# Comm.net
KiCad netlist of a schematic drawn in EAGLE
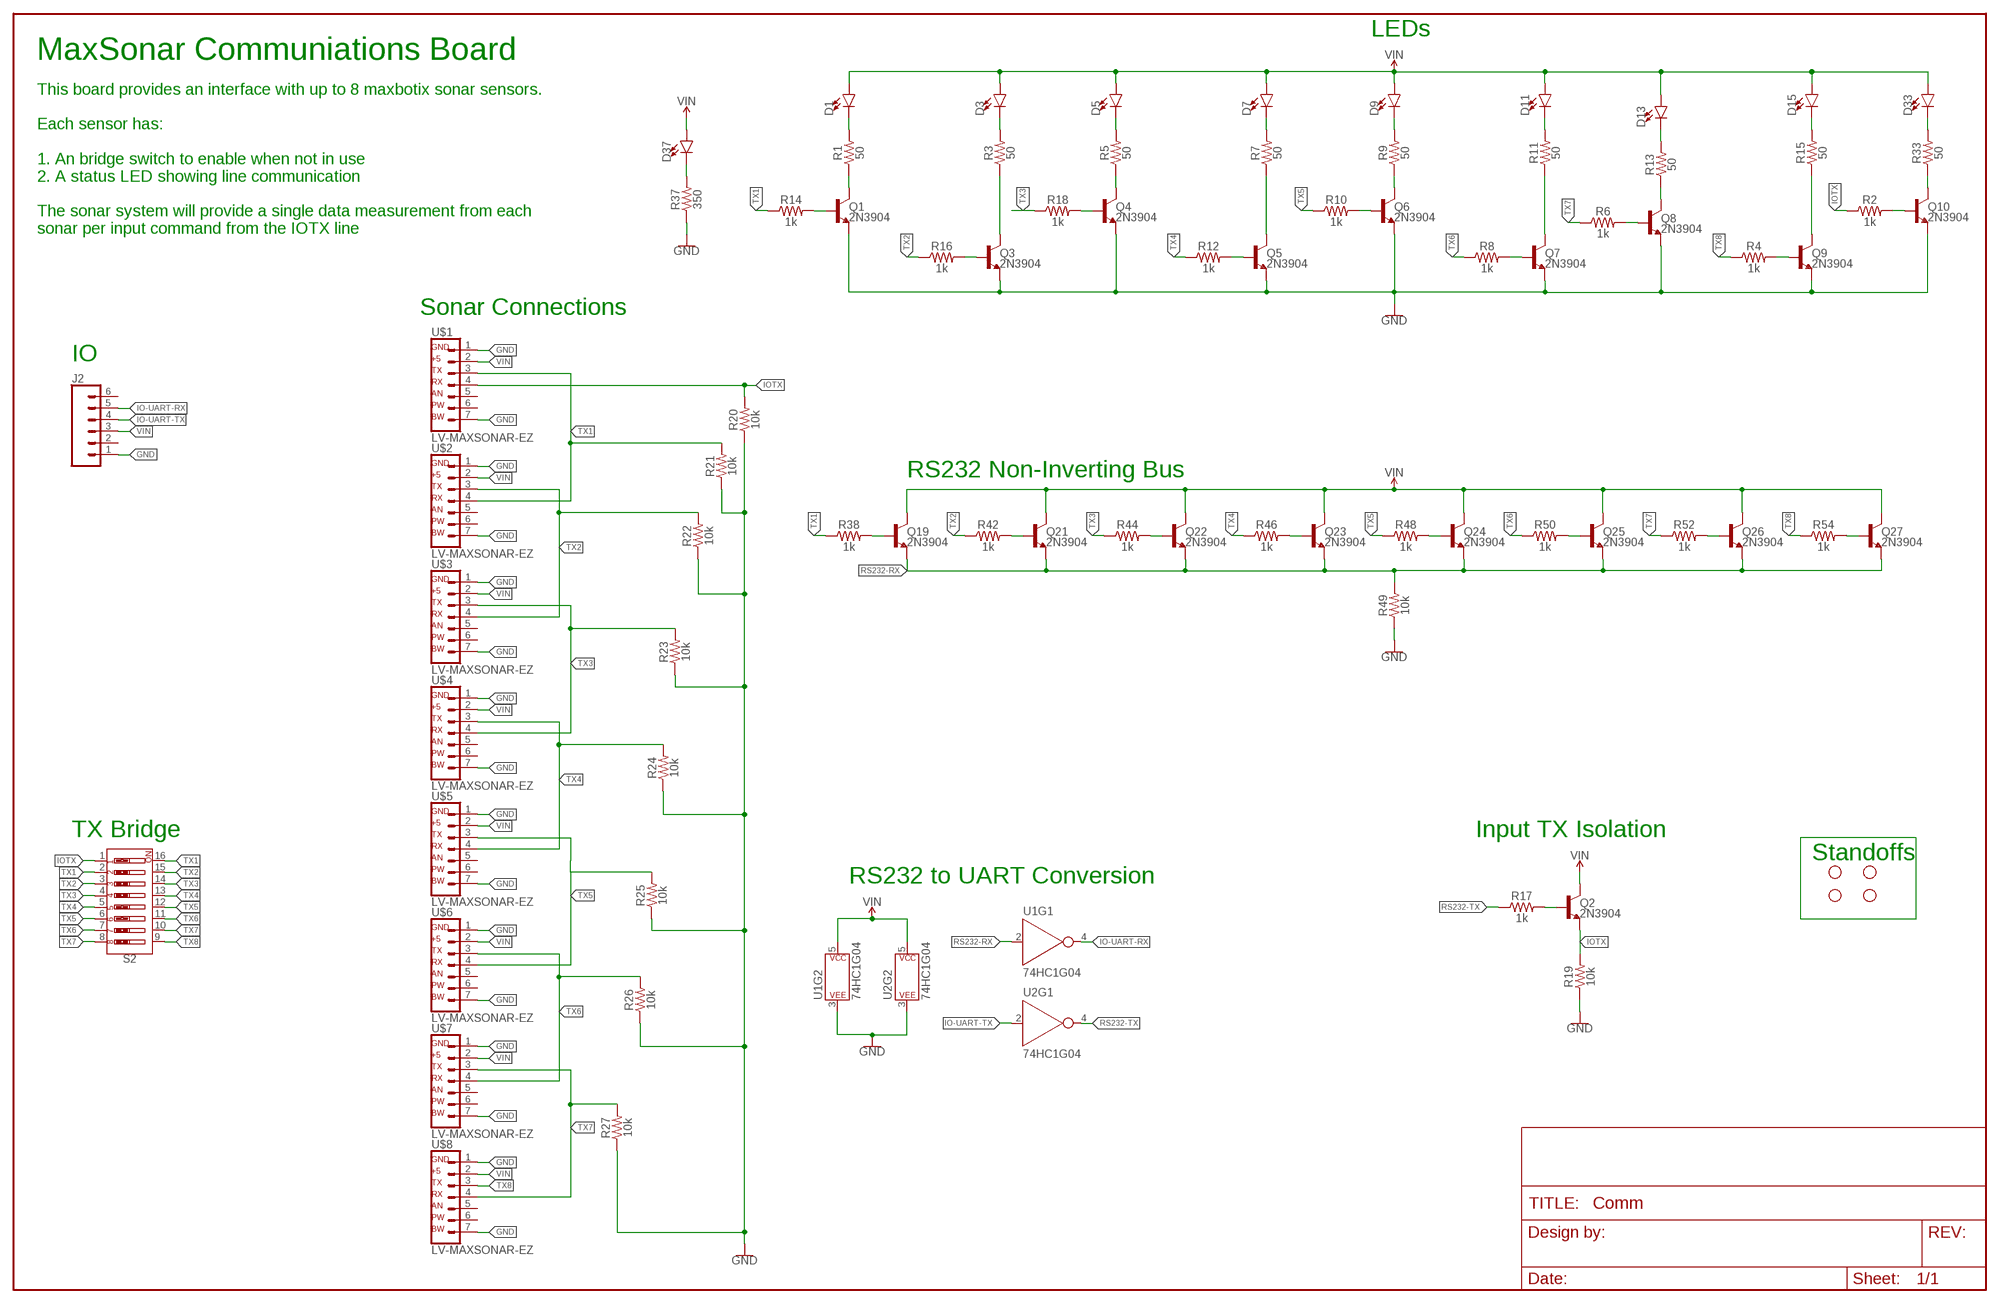
[diagram p0: schematic, sheet 1]

(export (version "E")
  (design (tool "Eeschema 10.0.6"))
  (components
    (comp (ref "D1")
      (value "LED0603")
      (footprint "eagle-import:LED-0603")
      (libsource (lib "eagle-import") (part "LED0603"))
    )
    (comp (ref "D3")
      (value "LED0603")
      (footprint "eagle-import:LED-0603")
      (libsource (lib "eagle-import") (part "LED0603"))
    )
    (comp (ref "D5")
      (value "LED0603")
      (footprint "eagle-import:LED-0603")
      (libsource (lib "eagle-import") (part "LED0603"))
    )
    (comp (ref "D7")
      (value "LED0603")
      (footprint "eagle-import:LED-0603")
      (libsource (lib "eagle-import") (part "LED0603"))
    )
    (comp (ref "D9")
      (value "LED0603")
      (footprint "eagle-import:LED-0603")
      (libsource (lib "eagle-import") (part "LED0603"))
    )
    (comp (ref "D11")
      (value "LED0603")
      (footprint "eagle-import:LED-0603")
      (libsource (lib "eagle-import") (part "LED0603"))
    )
    (comp (ref "D13")
      (value "LED0603")
      (footprint "eagle-import:LED-0603")
      (libsource (lib "eagle-import") (part "LED0603"))
    )
    (comp (ref "D15")
      (value "LED0603")
      (footprint "eagle-import:LED-0603")
      (libsource (lib "eagle-import") (part "LED0603"))
    )
    (comp (ref "D33")
      (value "LED0603")
      (footprint "eagle-import:LED-0603")
      (libsource (lib "eagle-import") (part "LED0603"))
    )
    (comp (ref "D37")
      (value "LED0603")
      (footprint "eagle-import:LED-0603")
      (libsource (lib "eagle-import") (part "LED0603"))
    )
    (comp (ref "FRAME1")
      (value "FRAME-LEDGER")
      (footprint "eagle-import:CREATIVE_COMMONS")
      (libsource (lib "eagle-import") (part "FRAME-LEDGER"))
    )
    (comp (ref "H1")
      (value "STAND-OFF")
      (footprint "eagle-import:STAND-OFF")
      (libsource (lib "eagle-import") (part "STAND-OFF"))
    )
    (comp (ref "H2")
      (value "STAND-OFF")
      (footprint "eagle-import:STAND-OFF")
      (libsource (lib "eagle-import") (part "STAND-OFF"))
    )
    (comp (ref "H3")
      (value "STAND-OFF")
      (footprint "eagle-import:STAND-OFF")
      (libsource (lib "eagle-import") (part "STAND-OFF"))
    )
    (comp (ref "H4")
      (value "STAND-OFF")
      (footprint "eagle-import:STAND-OFF")
      (libsource (lib "eagle-import") (part "STAND-OFF"))
    )
    (comp (ref "J2")
      (value "CONN_06POLAR")
      (footprint "eagle-import:MOLEX-1X6")
      (libsource (lib "eagle-import") (part "CONN_06POLAR"))
    )
    (comp (ref "Q1")
      (value "2N3904")
      (footprint "eagle-import:SOT23-3")
      (libsource (lib "eagle-import") (part "TRANS_NPN-MMBTA42"))
    )
    (comp (ref "Q2")
      (value "2N3904")
      (footprint "eagle-import:SOT23-3")
      (libsource (lib "eagle-import") (part "TRANS_NPN-MMBTA42"))
    )
    (comp (ref "Q3")
      (value "2N3904")
      (footprint "eagle-import:SOT23-3")
      (libsource (lib "eagle-import") (part "TRANS_NPN-MMBTA42"))
    )
    (comp (ref "Q4")
      (value "2N3904")
      (footprint "eagle-import:SOT23-3")
      (libsource (lib "eagle-import") (part "TRANS_NPN-MMBTA42"))
    )
    (comp (ref "Q5")
      (value "2N3904")
      (footprint "eagle-import:SOT23-3")
      (libsource (lib "eagle-import") (part "TRANS_NPN-MMBTA42"))
    )
    (comp (ref "Q6")
      (value "2N3904")
      (footprint "eagle-import:SOT23-3")
      (libsource (lib "eagle-import") (part "TRANS_NPN-MMBTA42"))
    )
    (comp (ref "Q7")
      (value "2N3904")
      (footprint "eagle-import:SOT23-3")
      (libsource (lib "eagle-import") (part "TRANS_NPN-MMBTA42"))
    )
    (comp (ref "Q8")
      (value "2N3904")
      (footprint "eagle-import:SOT23-3")
      (libsource (lib "eagle-import") (part "TRANS_NPN-MMBTA42"))
    )
    (comp (ref "Q9")
      (value "2N3904")
      (footprint "eagle-import:SOT23-3")
      (libsource (lib "eagle-import") (part "TRANS_NPN-MMBTA42"))
    )
    (comp (ref "Q10")
      (value "2N3904")
      (footprint "eagle-import:SOT23-3")
      (libsource (lib "eagle-import") (part "TRANS_NPN-MMBTA42"))
    )
    (comp (ref "Q19")
      (value "2N3904")
      (footprint "eagle-import:SOT23-3")
      (libsource (lib "eagle-import") (part "TRANS_NPN-MMBTA42"))
    )
    (comp (ref "Q21")
      (value "2N3904")
      (footprint "eagle-import:SOT23-3")
      (libsource (lib "eagle-import") (part "TRANS_NPN-MMBTA42"))
    )
    (comp (ref "Q22")
      (value "2N3904")
      (footprint "eagle-import:SOT23-3")
      (libsource (lib "eagle-import") (part "TRANS_NPN-MMBTA42"))
    )
    (comp (ref "Q23")
      (value "2N3904")
      (footprint "eagle-import:SOT23-3")
      (libsource (lib "eagle-import") (part "TRANS_NPN-MMBTA42"))
    )
    (comp (ref "Q24")
      (value "2N3904")
      (footprint "eagle-import:SOT23-3")
      (libsource (lib "eagle-import") (part "TRANS_NPN-MMBTA42"))
    )
    (comp (ref "Q25")
      (value "2N3904")
      (footprint "eagle-import:SOT23-3")
      (libsource (lib "eagle-import") (part "TRANS_NPN-MMBTA42"))
    )
    (comp (ref "Q26")
      (value "2N3904")
      (footprint "eagle-import:SOT23-3")
      (libsource (lib "eagle-import") (part "TRANS_NPN-MMBTA42"))
    )
    (comp (ref "Q27")
      (value "2N3904")
      (footprint "eagle-import:SOT23-3")
      (libsource (lib "eagle-import") (part "TRANS_NPN-MMBTA42"))
    )
    (comp (ref "R1")
      (value "50")
      (footprint "eagle-import:0805")
      (libsource (lib "eagle-import") (part "RESISTOR0805"))
    )
    (comp (ref "R2")
      (value "1k")
      (footprint "eagle-import:0805")
      (libsource (lib "eagle-import") (part "RESISTOR0805"))
    )
    (comp (ref "R3")
      (value "50")
      (footprint "eagle-import:0805")
      (libsource (lib "eagle-import") (part "RESISTOR0805"))
    )
    (comp (ref "R4")
      (value "1k")
      (footprint "eagle-import:0805")
      (libsource (lib "eagle-import") (part "RESISTOR0805"))
    )
    (comp (ref "R5")
      (value "50")
      (footprint "eagle-import:0805")
      (libsource (lib "eagle-import") (part "RESISTOR0805"))
    )
    (comp (ref "R6")
      (value "1k")
      (footprint "eagle-import:0805")
      (libsource (lib "eagle-import") (part "RESISTOR0805"))
    )
    (comp (ref "R7")
      (value "50")
      (footprint "eagle-import:0805")
      (libsource (lib "eagle-import") (part "RESISTOR0805"))
    )
    (comp (ref "R8")
      (value "1k")
      (footprint "eagle-import:0805")
      (libsource (lib "eagle-import") (part "RESISTOR0805"))
    )
    (comp (ref "R9")
      (value "50")
      (footprint "eagle-import:0805")
      (libsource (lib "eagle-import") (part "RESISTOR0805"))
    )
    (comp (ref "R10")
      (value "1k")
      (footprint "eagle-import:0805")
      (libsource (lib "eagle-import") (part "RESISTOR0805"))
    )
    (comp (ref "R11")
      (value "50")
      (footprint "eagle-import:0805")
      (libsource (lib "eagle-import") (part "RESISTOR0805"))
    )
    (comp (ref "R12")
      (value "1k")
      (footprint "eagle-import:0805")
      (libsource (lib "eagle-import") (part "RESISTOR0805"))
    )
    (comp (ref "R13")
      (value "50")
      (footprint "eagle-import:0805")
      (libsource (lib "eagle-import") (part "RESISTOR0805"))
    )
    (comp (ref "R14")
      (value "1k")
      (footprint "eagle-import:0805")
      (libsource (lib "eagle-import") (part "RESISTOR0805"))
    )
    (comp (ref "R15")
      (value "50")
      (footprint "eagle-import:0805")
      (libsource (lib "eagle-import") (part "RESISTOR0805"))
    )
    (comp (ref "R16")
      (value "1k")
      (footprint "eagle-import:0805")
      (libsource (lib "eagle-import") (part "RESISTOR0805"))
    )
    (comp (ref "R17")
      (value "1k")
      (footprint "eagle-import:0805")
      (libsource (lib "eagle-import") (part "RESISTOR0805"))
    )
    (comp (ref "R18")
      (value "1k")
      (footprint "eagle-import:0805")
      (libsource (lib "eagle-import") (part "RESISTOR0805"))
    )
    (comp (ref "R19")
      (value "10k")
      (footprint "eagle-import:0805")
      (libsource (lib "eagle-import") (part "RESISTOR0805"))
    )
    (comp (ref "R20")
      (value "10k")
      (footprint "eagle-import:0805")
      (libsource (lib "eagle-import") (part "RESISTOR0805"))
    )
    (comp (ref "R21")
      (value "10k")
      (footprint "eagle-import:0805")
      (libsource (lib "eagle-import") (part "RESISTOR0805"))
    )
    (comp (ref "R22")
      (value "10k")
      (footprint "eagle-import:0805")
      (libsource (lib "eagle-import") (part "RESISTOR0805"))
    )
    (comp (ref "R23")
      (value "10k")
      (footprint "eagle-import:0805")
      (libsource (lib "eagle-import") (part "RESISTOR0805"))
    )
    (comp (ref "R24")
      (value "10k")
      (footprint "eagle-import:0805")
      (libsource (lib "eagle-import") (part "RESISTOR0805"))
    )
    (comp (ref "R25")
      (value "10k")
      (footprint "eagle-import:0805")
      (libsource (lib "eagle-import") (part "RESISTOR0805"))
    )
    (comp (ref "R26")
      (value "10k")
      (footprint "eagle-import:0805")
      (libsource (lib "eagle-import") (part "RESISTOR0805"))
    )
    (comp (ref "R27")
      (value "10k")
      (footprint "eagle-import:0805")
      (libsource (lib "eagle-import") (part "RESISTOR0805"))
    )
    (comp (ref "R33")
      (value "50")
      (footprint "eagle-import:0805")
      (libsource (lib "eagle-import") (part "RESISTOR0805"))
    )
    (comp (ref "R37")
      (value "350")
      (footprint "eagle-import:0805")
      (libsource (lib "eagle-import") (part "RESISTOR0805"))
    )
    (comp (ref "R38")
      (value "1k")
      (footprint "eagle-import:0805")
      (libsource (lib "eagle-import") (part "RESISTOR0805"))
    )
    (comp (ref "R42")
      (value "1k")
      (footprint "eagle-import:0805")
      (libsource (lib "eagle-import") (part "RESISTOR0805"))
    )
    (comp (ref "R44")
      (value "1k")
      (footprint "eagle-import:0805")
      (libsource (lib "eagle-import") (part "RESISTOR0805"))
    )
    (comp (ref "R46")
      (value "1k")
      (footprint "eagle-import:0805")
      (libsource (lib "eagle-import") (part "RESISTOR0805"))
    )
    (comp (ref "R48")
      (value "1k")
      (footprint "eagle-import:0805")
      (libsource (lib "eagle-import") (part "RESISTOR0805"))
    )
    (comp (ref "R49")
      (value "10k")
      (footprint "eagle-import:0805")
      (libsource (lib "eagle-import") (part "RESISTOR0805"))
    )
    (comp (ref "R50")
      (value "1k")
      (footprint "eagle-import:0805")
      (libsource (lib "eagle-import") (part "RESISTOR0805"))
    )
    (comp (ref "R52")
      (value "1k")
      (footprint "eagle-import:0805")
      (libsource (lib "eagle-import") (part "RESISTOR0805"))
    )
    (comp (ref "R54")
      (value "1k")
      (footprint "eagle-import:0805")
      (libsource (lib "eagle-import") (part "RESISTOR0805"))
    )
    (comp (ref "S2")
      (value "DIP-08-PTH")
      (footprint "eagle-import:DIPSWITCH-08")
      (libsource (lib "eagle-import") (part "DIP-08-PTH"))
    )
    (comp (ref "U$1")
      (value "LV-MAXSONAR-EZ")
      (footprint "eagle-import:1X07")
      (libsource (lib "eagle-import") (part "LV-MAXSONAR-EZ"))
    )
    (comp (ref "U$2")
      (value "LV-MAXSONAR-EZ")
      (footprint "eagle-import:1X07")
      (libsource (lib "eagle-import") (part "LV-MAXSONAR-EZ"))
    )
    (comp (ref "U$3")
      (value "LV-MAXSONAR-EZ")
      (footprint "eagle-import:1X07")
      (libsource (lib "eagle-import") (part "LV-MAXSONAR-EZ"))
    )
    (comp (ref "U$4")
      (value "LV-MAXSONAR-EZ")
      (footprint "eagle-import:1X07")
      (libsource (lib "eagle-import") (part "LV-MAXSONAR-EZ"))
    )
    (comp (ref "U$5")
      (value "LV-MAXSONAR-EZ")
      (footprint "eagle-import:1X07")
      (libsource (lib "eagle-import") (part "LV-MAXSONAR-EZ"))
    )
    (comp (ref "U$6")
      (value "LV-MAXSONAR-EZ")
      (footprint "eagle-import:1X07")
      (libsource (lib "eagle-import") (part "LV-MAXSONAR-EZ"))
    )
    (comp (ref "U$7")
      (value "LV-MAXSONAR-EZ")
      (footprint "eagle-import:1X07")
      (libsource (lib "eagle-import") (part "LV-MAXSONAR-EZ"))
    )
    (comp (ref "U$8")
      (value "LV-MAXSONAR-EZ")
      (footprint "eagle-import:1X07")
      (libsource (lib "eagle-import") (part "LV-MAXSONAR-EZ"))
    )
    (comp (ref "U1")
      (value "74HC1G04")
      (footprint "eagle-import:SOT353")
      (libsource (lib "eagle-import") (part "741G04HC"))
    )
    (comp (ref "U2")
      (value "74HC1G04")
      (footprint "eagle-import:SOT353")
      (libsource (lib "eagle-import") (part "741G04HC"))
    )
  )
  (nets
    (net (code "1") (name "GND") (class "Default")
      (node (ref "J2") (pin "1") (pinfunction "1_1") (pintype "passive"))
      (node (ref "Q1") (pin "2") (pinfunction "E_2") (pintype "passive"))
      (node (ref "Q10") (pin "2") (pinfunction "E_2") (pintype "passive"))
      (node (ref "Q3") (pin "2") (pinfunction "E_2") (pintype "passive"))
      (node (ref "Q4") (pin "2") (pinfunction "E_2") (pintype "passive"))
      (node (ref "Q5") (pin "2") (pinfunction "E_2") (pintype "passive"))
      (node (ref "Q6") (pin "2") (pinfunction "E_2") (pintype "passive"))
      (node (ref "Q7") (pin "2") (pinfunction "E_2") (pintype "passive"))
      (node (ref "Q8") (pin "2") (pinfunction "E_2") (pintype "passive"))
      (node (ref "Q9") (pin "2") (pinfunction "E_2") (pintype "passive"))
      (node (ref "R19") (pin "1") (pinfunction "1_1") (pintype "passive"))
      (node (ref "R20") (pin "1") (pinfunction "1_1") (pintype "passive"))
      (node (ref "R21") (pin "1") (pinfunction "1_1") (pintype "passive"))
      (node (ref "R22") (pin "1") (pinfunction "1_1") (pintype "passive"))
      (node (ref "R23") (pin "1") (pinfunction "1_1") (pintype "passive"))
      (node (ref "R24") (pin "1") (pinfunction "1_1") (pintype "passive"))
      (node (ref "R25") (pin "1") (pinfunction "1_1") (pintype "passive"))
      (node (ref "R26") (pin "1") (pinfunction "1_1") (pintype "passive"))
      (node (ref "R27") (pin "1") (pinfunction "1_1") (pintype "passive"))
      (node (ref "R37") (pin "1") (pinfunction "1_1") (pintype "passive"))
      (node (ref "R49") (pin "1") (pinfunction "1_1") (pintype "passive"))
      (node (ref "U$1") (pin "1") (pinfunction "GND_1") (pintype "passive"))
      (node (ref "U$1") (pin "7") (pinfunction "BW_7") (pintype "passive"))
      (node (ref "U$2") (pin "1") (pinfunction "GND_1") (pintype "passive"))
      (node (ref "U$2") (pin "7") (pinfunction "BW_7") (pintype "passive"))
      (node (ref "U$3") (pin "1") (pinfunction "GND_1") (pintype "passive"))
      (node (ref "U$3") (pin "7") (pinfunction "BW_7") (pintype "passive"))
      (node (ref "U$4") (pin "1") (pinfunction "GND_1") (pintype "passive"))
      (node (ref "U$4") (pin "7") (pinfunction "BW_7") (pintype "passive"))
      (node (ref "U$5") (pin "1") (pinfunction "GND_1") (pintype "passive"))
      (node (ref "U$5") (pin "7") (pinfunction "BW_7") (pintype "passive"))
      (node (ref "U$6") (pin "1") (pinfunction "GND_1") (pintype "passive"))
      (node (ref "U$6") (pin "7") (pinfunction "BW_7") (pintype "passive"))
      (node (ref "U$7") (pin "1") (pinfunction "GND_1") (pintype "passive"))
      (node (ref "U$7") (pin "7") (pinfunction "BW_7") (pintype "passive"))
      (node (ref "U$8") (pin "1") (pinfunction "GND_1") (pintype "passive"))
      (node (ref "U$8") (pin "7") (pinfunction "BW_7") (pintype "passive"))
      (node (ref "U1") (pin "3") (pinfunction "P$V-_3") (pintype "bidirectional"))
      (node (ref "U2") (pin "3") (pinfunction "P$V-_3") (pintype "bidirectional"))
    )
    (net (code "2") (name "IO-UART-RX") (class "Default")
      (node (ref "J2") (pin "5") (pinfunction "5_5") (pintype "passive"))
      (node (ref "U1") (pin "4") (pinfunction "Y_4") (pintype "bidirectional"))
    )
    (net (code "3") (name "IO-UART-TX") (class "Default")
      (node (ref "J2") (pin "4") (pinfunction "4_4") (pintype "passive"))
      (node (ref "U2") (pin "2") (pinfunction "A_2") (pintype "bidirectional"))
    )
    (net (code "4") (name "IOTX") (class "Default")
      (node (ref "Q2") (pin "2") (pinfunction "E_2") (pintype "passive"))
      (node (ref "R19") (pin "2") (pinfunction "2_2") (pintype "passive"))
      (node (ref "R2") (pin "1") (pinfunction "1_1") (pintype "passive"))
      (node (ref "R20") (pin "2") (pinfunction "2_2") (pintype "passive"))
      (node (ref "S2") (pin "1") (pinfunction "1_1") (pintype "passive"))
      (node (ref "U$1") (pin "4") (pinfunction "RX_4") (pintype "passive"))
    )
    (net (code "5") (name "Net-(D1-PadC)") (class "Default")
      (node (ref "D1") (pin "C") (pinfunction "C_C") (pintype "passive"))
      (node (ref "R1") (pin "2") (pinfunction "2_2") (pintype "passive"))
    )
    (net (code "6") (name "Net-(D3-PadC)") (class "Default")
      (node (ref "D3") (pin "C") (pinfunction "C_C") (pintype "passive"))
      (node (ref "R3") (pin "2") (pinfunction "2_2") (pintype "passive"))
    )
    (net (code "7") (name "Net-(D5-PadC)") (class "Default")
      (node (ref "D5") (pin "C") (pinfunction "C_C") (pintype "passive"))
      (node (ref "R5") (pin "2") (pinfunction "2_2") (pintype "passive"))
    )
    (net (code "8") (name "Net-(D7-PadC)") (class "Default")
      (node (ref "D7") (pin "C") (pinfunction "C_C") (pintype "passive"))
      (node (ref "R7") (pin "2") (pinfunction "2_2") (pintype "passive"))
    )
    (net (code "9") (name "Net-(D9-PadC)") (class "Default")
      (node (ref "D9") (pin "C") (pinfunction "C_C") (pintype "passive"))
      (node (ref "R9") (pin "2") (pinfunction "2_2") (pintype "passive"))
    )
    (net (code "10") (name "Net-(D11-PadC)") (class "Default")
      (node (ref "D11") (pin "C") (pinfunction "C_C") (pintype "passive"))
      (node (ref "R11") (pin "2") (pinfunction "2_2") (pintype "passive"))
    )
    (net (code "11") (name "Net-(D13-PadC)") (class "Default")
      (node (ref "D13") (pin "C") (pinfunction "C_C") (pintype "passive"))
      (node (ref "R13") (pin "2") (pinfunction "2_2") (pintype "passive"))
    )
    (net (code "12") (name "Net-(D15-PadC)") (class "Default")
      (node (ref "D15") (pin "C") (pinfunction "C_C") (pintype "passive"))
      (node (ref "R15") (pin "2") (pinfunction "2_2") (pintype "passive"))
    )
    (net (code "13") (name "Net-(D33-PadC)") (class "Default")
      (node (ref "D33") (pin "C") (pinfunction "C_C") (pintype "passive"))
      (node (ref "R33") (pin "2") (pinfunction "2_2") (pintype "passive"))
    )
    (net (code "14") (name "Net-(D37-PadC)") (class "Default")
      (node (ref "D37") (pin "C") (pinfunction "C_C") (pintype "passive"))
      (node (ref "R37") (pin "2") (pinfunction "2_2") (pintype "passive"))
    )
    (net (code "15") (name "Net-(Q1-B)") (class "Default")
      (node (ref "Q1") (pin "1") (pinfunction "B_1") (pintype "passive"))
      (node (ref "R14") (pin "2") (pinfunction "2_2") (pintype "passive"))
    )
    (net (code "16") (name "Net-(Q1-C)") (class "Default")
      (node (ref "Q1") (pin "3") (pinfunction "C_3") (pintype "passive"))
      (node (ref "R1") (pin "1") (pinfunction "1_1") (pintype "passive"))
    )
    (net (code "17") (name "Net-(Q2-B)") (class "Default")
      (node (ref "Q2") (pin "1") (pinfunction "B_1") (pintype "passive"))
      (node (ref "R17") (pin "2") (pinfunction "2_2") (pintype "passive"))
    )
    (net (code "18") (name "Net-(Q3-B)") (class "Default")
      (node (ref "Q3") (pin "1") (pinfunction "B_1") (pintype "passive"))
      (node (ref "R16") (pin "2") (pinfunction "2_2") (pintype "passive"))
    )
    (net (code "19") (name "Net-(Q3-C)") (class "Default")
      (node (ref "Q3") (pin "3") (pinfunction "C_3") (pintype "passive"))
      (node (ref "R3") (pin "1") (pinfunction "1_1") (pintype "passive"))
    )
    (net (code "20") (name "Net-(Q4-B)") (class "Default")
      (node (ref "Q4") (pin "1") (pinfunction "B_1") (pintype "passive"))
      (node (ref "R18") (pin "2") (pinfunction "2_2") (pintype "passive"))
    )
    (net (code "21") (name "Net-(Q4-C)") (class "Default")
      (node (ref "Q4") (pin "3") (pinfunction "C_3") (pintype "passive"))
      (node (ref "R5") (pin "1") (pinfunction "1_1") (pintype "passive"))
    )
    (net (code "22") (name "Net-(Q5-B)") (class "Default")
      (node (ref "Q5") (pin "1") (pinfunction "B_1") (pintype "passive"))
      (node (ref "R12") (pin "2") (pinfunction "2_2") (pintype "passive"))
    )
    (net (code "23") (name "Net-(Q5-C)") (class "Default")
      (node (ref "Q5") (pin "3") (pinfunction "C_3") (pintype "passive"))
      (node (ref "R7") (pin "1") (pinfunction "1_1") (pintype "passive"))
    )
    (net (code "24") (name "Net-(Q6-B)") (class "Default")
      (node (ref "Q6") (pin "1") (pinfunction "B_1") (pintype "passive"))
      (node (ref "R10") (pin "2") (pinfunction "2_2") (pintype "passive"))
    )
    (net (code "25") (name "Net-(Q6-C)") (class "Default")
      (node (ref "Q6") (pin "3") (pinfunction "C_3") (pintype "passive"))
      (node (ref "R9") (pin "1") (pinfunction "1_1") (pintype "passive"))
    )
    (net (code "26") (name "Net-(Q7-B)") (class "Default")
      (node (ref "Q7") (pin "1") (pinfunction "B_1") (pintype "passive"))
      (node (ref "R8") (pin "2") (pinfunction "2_2") (pintype "passive"))
    )
    (net (code "27") (name "Net-(Q7-C)") (class "Default")
      (node (ref "Q7") (pin "3") (pinfunction "C_3") (pintype "passive"))
      (node (ref "R11") (pin "1") (pinfunction "1_1") (pintype "passive"))
    )
    (net (code "28") (name "Net-(Q8-B)") (class "Default")
      (node (ref "Q8") (pin "1") (pinfunction "B_1") (pintype "passive"))
      (node (ref "R6") (pin "2") (pinfunction "2_2") (pintype "passive"))
    )
    (net (code "29") (name "Net-(Q8-C)") (class "Default")
      (node (ref "Q8") (pin "3") (pinfunction "C_3") (pintype "passive"))
      (node (ref "R13") (pin "1") (pinfunction "1_1") (pintype "passive"))
    )
    (net (code "30") (name "Net-(Q9-B)") (class "Default")
      (node (ref "Q9") (pin "1") (pinfunction "B_1") (pintype "passive"))
      (node (ref "R4") (pin "2") (pinfunction "2_2") (pintype "passive"))
    )
    (net (code "31") (name "Net-(Q9-C)") (class "Default")
      (node (ref "Q9") (pin "3") (pinfunction "C_3") (pintype "passive"))
      (node (ref "R15") (pin "1") (pinfunction "1_1") (pintype "passive"))
    )
    (net (code "32") (name "Net-(Q10-B)") (class "Default")
      (node (ref "Q10") (pin "1") (pinfunction "B_1") (pintype "passive"))
      (node (ref "R2") (pin "2") (pinfunction "2_2") (pintype "passive"))
    )
    (net (code "33") (name "Net-(Q10-C)") (class "Default")
      (node (ref "Q10") (pin "3") (pinfunction "C_3") (pintype "passive"))
      (node (ref "R33") (pin "1") (pinfunction "1_1") (pintype "passive"))
    )
    (net (code "34") (name "Net-(Q19-B)") (class "Default")
      (node (ref "Q19") (pin "1") (pinfunction "B_1") (pintype "passive"))
      (node (ref "R38") (pin "2") (pinfunction "2_2") (pintype "passive"))
    )
    (net (code "35") (name "Net-(Q21-B)") (class "Default")
      (node (ref "Q21") (pin "1") (pinfunction "B_1") (pintype "passive"))
      (node (ref "R42") (pin "2") (pinfunction "2_2") (pintype "passive"))
    )
    (net (code "36") (name "Net-(Q22-B)") (class "Default")
      (node (ref "Q22") (pin "1") (pinfunction "B_1") (pintype "passive"))
      (node (ref "R44") (pin "2") (pinfunction "2_2") (pintype "passive"))
    )
    (net (code "37") (name "Net-(Q23-B)") (class "Default")
      (node (ref "Q23") (pin "1") (pinfunction "B_1") (pintype "passive"))
      (node (ref "R46") (pin "2") (pinfunction "2_2") (pintype "passive"))
    )
    (net (code "38") (name "Net-(Q24-B)") (class "Default")
      (node (ref "Q24") (pin "1") (pinfunction "B_1") (pintype "passive"))
      (node (ref "R48") (pin "2") (pinfunction "2_2") (pintype "passive"))
    )
    (net (code "39") (name "Net-(Q25-B)") (class "Default")
      (node (ref "Q25") (pin "1") (pinfunction "B_1") (pintype "passive"))
      (node (ref "R50") (pin "2") (pinfunction "2_2") (pintype "passive"))
    )
    (net (code "40") (name "Net-(Q26-B)") (class "Default")
      (node (ref "Q26") (pin "1") (pinfunction "B_1") (pintype "passive"))
      (node (ref "R52") (pin "2") (pinfunction "2_2") (pintype "passive"))
    )
    (net (code "41") (name "Net-(Q27-B)") (class "Default")
      (node (ref "Q27") (pin "1") (pinfunction "B_1") (pintype "passive"))
      (node (ref "R54") (pin "2") (pinfunction "2_2") (pintype "passive"))
    )
    (net (code "42") (name "RS232-RX") (class "Default")
      (node (ref "Q19") (pin "2") (pinfunction "E_2") (pintype "passive"))
      (node (ref "Q21") (pin "2") (pinfunction "E_2") (pintype "passive"))
      (node (ref "Q22") (pin "2") (pinfunction "E_2") (pintype "passive"))
      (node (ref "Q23") (pin "2") (pinfunction "E_2") (pintype "passive"))
      (node (ref "Q24") (pin "2") (pinfunction "E_2") (pintype "passive"))
      (node (ref "Q25") (pin "2") (pinfunction "E_2") (pintype "passive"))
      (node (ref "Q26") (pin "2") (pinfunction "E_2") (pintype "passive"))
      (node (ref "Q27") (pin "2") (pinfunction "E_2") (pintype "passive"))
      (node (ref "R49") (pin "2") (pinfunction "2_2") (pintype "passive"))
      (node (ref "U1") (pin "2") (pinfunction "A_2") (pintype "bidirectional"))
    )
    (net (code "43") (name "RS232-TX") (class "Default")
      (node (ref "R17") (pin "1") (pinfunction "1_1") (pintype "passive"))
      (node (ref "U2") (pin "4") (pinfunction "Y_4") (pintype "bidirectional"))
    )
    (net (code "44") (name "TX1") (class "Default")
      (node (ref "R14") (pin "1") (pinfunction "1_1") (pintype "passive"))
      (node (ref "R21") (pin "2") (pinfunction "2_2") (pintype "passive"))
      (node (ref "R38") (pin "1") (pinfunction "1_1") (pintype "passive"))
      (node (ref "S2") (pin "16") (pinfunction "16_16") (pintype "passive"))
      (node (ref "S2") (pin "2") (pinfunction "2_2") (pintype "passive"))
      (node (ref "U$1") (pin "3") (pinfunction "TX_3") (pintype "passive"))
      (node (ref "U$2") (pin "4") (pinfunction "RX_4") (pintype "passive"))
    )
    (net (code "45") (name "TX2") (class "Default")
      (node (ref "R16") (pin "1") (pinfunction "1_1") (pintype "passive"))
      (node (ref "R22") (pin "2") (pinfunction "2_2") (pintype "passive"))
      (node (ref "R42") (pin "1") (pinfunction "1_1") (pintype "passive"))
      (node (ref "S2") (pin "15") (pinfunction "15_15") (pintype "passive"))
      (node (ref "S2") (pin "3") (pinfunction "3_3") (pintype "passive"))
      (node (ref "U$2") (pin "3") (pinfunction "TX_3") (pintype "passive"))
      (node (ref "U$3") (pin "4") (pinfunction "RX_4") (pintype "passive"))
    )
    (net (code "46") (name "TX3") (class "Default")
      (node (ref "R18") (pin "1") (pinfunction "1_1") (pintype "passive"))
      (node (ref "R23") (pin "2") (pinfunction "2_2") (pintype "passive"))
      (node (ref "R44") (pin "1") (pinfunction "1_1") (pintype "passive"))
      (node (ref "S2") (pin "14") (pinfunction "14_14") (pintype "passive"))
      (node (ref "S2") (pin "4") (pinfunction "4_4") (pintype "passive"))
      (node (ref "U$3") (pin "3") (pinfunction "TX_3") (pintype "passive"))
      (node (ref "U$4") (pin "4") (pinfunction "RX_4") (pintype "passive"))
    )
    (net (code "47") (name "TX4") (class "Default")
      (node (ref "R12") (pin "1") (pinfunction "1_1") (pintype "passive"))
      (node (ref "R24") (pin "2") (pinfunction "2_2") (pintype "passive"))
      (node (ref "R46") (pin "1") (pinfunction "1_1") (pintype "passive"))
      (node (ref "S2") (pin "13") (pinfunction "13_13") (pintype "passive"))
      (node (ref "S2") (pin "5") (pinfunction "5_5") (pintype "passive"))
      (node (ref "U$4") (pin "3") (pinfunction "TX_3") (pintype "passive"))
      (node (ref "U$5") (pin "4") (pinfunction "RX_4") (pintype "passive"))
    )
    (net (code "48") (name "TX5") (class "Default")
      (node (ref "R10") (pin "1") (pinfunction "1_1") (pintype "passive"))
      (node (ref "R25") (pin "2") (pinfunction "2_2") (pintype "passive"))
      (node (ref "R48") (pin "1") (pinfunction "1_1") (pintype "passive"))
      (node (ref "S2") (pin "12") (pinfunction "12_12") (pintype "passive"))
      (node (ref "S2") (pin "6") (pinfunction "6_6") (pintype "passive"))
      (node (ref "U$5") (pin "3") (pinfunction "TX_3") (pintype "passive"))
      (node (ref "U$6") (pin "4") (pinfunction "RX_4") (pintype "passive"))
    )
    (net (code "49") (name "TX6") (class "Default")
      (node (ref "R26") (pin "2") (pinfunction "2_2") (pintype "passive"))
      (node (ref "R50") (pin "1") (pinfunction "1_1") (pintype "passive"))
      (node (ref "R8") (pin "1") (pinfunction "1_1") (pintype "passive"))
      (node (ref "S2") (pin "11") (pinfunction "11_11") (pintype "passive"))
      (node (ref "S2") (pin "7") (pinfunction "7_7") (pintype "passive"))
      (node (ref "U$6") (pin "3") (pinfunction "TX_3") (pintype "passive"))
      (node (ref "U$7") (pin "4") (pinfunction "RX_4") (pintype "passive"))
    )
    (net (code "50") (name "TX7") (class "Default")
      (node (ref "R27") (pin "2") (pinfunction "2_2") (pintype "passive"))
      (node (ref "R52") (pin "1") (pinfunction "1_1") (pintype "passive"))
      (node (ref "R6") (pin "1") (pinfunction "1_1") (pintype "passive"))
      (node (ref "S2") (pin "10") (pinfunction "10_10") (pintype "passive"))
      (node (ref "S2") (pin "8") (pinfunction "8_8") (pintype "passive"))
      (node (ref "U$7") (pin "3") (pinfunction "TX_3") (pintype "passive"))
      (node (ref "U$8") (pin "4") (pinfunction "RX_4") (pintype "passive"))
    )
    (net (code "51") (name "TX8") (class "Default")
      (node (ref "R4") (pin "1") (pinfunction "1_1") (pintype "passive"))
      (node (ref "R54") (pin "1") (pinfunction "1_1") (pintype "passive"))
      (node (ref "S2") (pin "9") (pinfunction "9_9") (pintype "passive"))
      (node (ref "U$8") (pin "3") (pinfunction "TX_3") (pintype "passive"))
    )
    (net (code "52") (name "VIN") (class "Default")
      (node (ref "D1") (pin "A") (pinfunction "A_A") (pintype "passive"))
      (node (ref "D11") (pin "A") (pinfunction "A_A") (pintype "passive"))
      (node (ref "D13") (pin "A") (pinfunction "A_A") (pintype "passive"))
      (node (ref "D15") (pin "A") (pinfunction "A_A") (pintype "passive"))
      (node (ref "D3") (pin "A") (pinfunction "A_A") (pintype "passive"))
      (node (ref "D33") (pin "A") (pinfunction "A_A") (pintype "passive"))
      (node (ref "D37") (pin "A") (pinfunction "A_A") (pintype "passive"))
      (node (ref "D5") (pin "A") (pinfunction "A_A") (pintype "passive"))
      (node (ref "D7") (pin "A") (pinfunction "A_A") (pintype "passive"))
      (node (ref "D9") (pin "A") (pinfunction "A_A") (pintype "passive"))
      (node (ref "J2") (pin "3") (pinfunction "3_3") (pintype "passive"))
      (node (ref "Q19") (pin "3") (pinfunction "C_3") (pintype "passive"))
      (node (ref "Q2") (pin "3") (pinfunction "C_3") (pintype "passive"))
      (node (ref "Q21") (pin "3") (pinfunction "C_3") (pintype "passive"))
      (node (ref "Q22") (pin "3") (pinfunction "C_3") (pintype "passive"))
      (node (ref "Q23") (pin "3") (pinfunction "C_3") (pintype "passive"))
      (node (ref "Q24") (pin "3") (pinfunction "C_3") (pintype "passive"))
      (node (ref "Q25") (pin "3") (pinfunction "C_3") (pintype "passive"))
      (node (ref "Q26") (pin "3") (pinfunction "C_3") (pintype "passive"))
      (node (ref "Q27") (pin "3") (pinfunction "C_3") (pintype "passive"))
      (node (ref "U$1") (pin "2") (pinfunction "+5_2") (pintype "passive"))
      (node (ref "U$2") (pin "2") (pinfunction "+5_2") (pintype "passive"))
      (node (ref "U$3") (pin "2") (pinfunction "+5_2") (pintype "passive"))
      (node (ref "U$4") (pin "2") (pinfunction "+5_2") (pintype "passive"))
      (node (ref "U$5") (pin "2") (pinfunction "+5_2") (pintype "passive"))
      (node (ref "U$6") (pin "2") (pinfunction "+5_2") (pintype "passive"))
      (node (ref "U$7") (pin "2") (pinfunction "+5_2") (pintype "passive"))
      (node (ref "U$8") (pin "2") (pinfunction "+5_2") (pintype "passive"))
      (node (ref "U1") (pin "5") (pinfunction "P$V+_5") (pintype "bidirectional"))
      (node (ref "U2") (pin "5") (pinfunction "P$V+_5") (pintype "bidirectional"))
    )
    (net (code "53") (name "unconnected-(J2-Pad2)") (class "Default")
      (node (ref "J2") (pin "2") (pinfunction "2_2") (pintype "passive"))
    )
    (net (code "54") (name "unconnected-(J2-Pad6)") (class "Default")
      (node (ref "J2") (pin "6") (pinfunction "6_6") (pintype "passive"))
    )
    (net (code "55") (name "unconnected-(U$1-AN-Pad5)") (class "Default")
      (node (ref "U$1") (pin "5") (pinfunction "AN_5") (pintype "passive"))
    )
    (net (code "56") (name "unconnected-(U$1-PW-Pad6)") (class "Default")
      (node (ref "U$1") (pin "6") (pinfunction "PW_6") (pintype "passive"))
    )
    (net (code "57") (name "unconnected-(U$2-AN-Pad5)") (class "Default")
      (node (ref "U$2") (pin "5") (pinfunction "AN_5") (pintype "passive"))
    )
    (net (code "58") (name "unconnected-(U$2-PW-Pad6)") (class "Default")
      (node (ref "U$2") (pin "6") (pinfunction "PW_6") (pintype "passive"))
    )
    (net (code "59") (name "unconnected-(U$3-AN-Pad5)") (class "Default")
      (node (ref "U$3") (pin "5") (pinfunction "AN_5") (pintype "passive"))
    )
    (net (code "60") (name "unconnected-(U$3-PW-Pad6)") (class "Default")
      (node (ref "U$3") (pin "6") (pinfunction "PW_6") (pintype "passive"))
    )
    (net (code "61") (name "unconnected-(U$4-AN-Pad5)") (class "Default")
      (node (ref "U$4") (pin "5") (pinfunction "AN_5") (pintype "passive"))
    )
    (net (code "62") (name "unconnected-(U$4-PW-Pad6)") (class "Default")
      (node (ref "U$4") (pin "6") (pinfunction "PW_6") (pintype "passive"))
    )
    (net (code "63") (name "unconnected-(U$5-AN-Pad5)") (class "Default")
      (node (ref "U$5") (pin "5") (pinfunction "AN_5") (pintype "passive"))
    )
    (net (code "64") (name "unconnected-(U$5-PW-Pad6)") (class "Default")
      (node (ref "U$5") (pin "6") (pinfunction "PW_6") (pintype "passive"))
    )
    (net (code "65") (name "unconnected-(U$6-AN-Pad5)") (class "Default")
      (node (ref "U$6") (pin "5") (pinfunction "AN_5") (pintype "passive"))
    )
    (net (code "66") (name "unconnected-(U$6-PW-Pad6)") (class "Default")
      (node (ref "U$6") (pin "6") (pinfunction "PW_6") (pintype "passive"))
    )
    (net (code "67") (name "unconnected-(U$7-AN-Pad5)") (class "Default")
      (node (ref "U$7") (pin "5") (pinfunction "AN_5") (pintype "passive"))
    )
    (net (code "68") (name "unconnected-(U$7-PW-Pad6)") (class "Default")
      (node (ref "U$7") (pin "6") (pinfunction "PW_6") (pintype "passive"))
    )
    (net (code "69") (name "unconnected-(U$8-AN-Pad5)") (class "Default")
      (node (ref "U$8") (pin "5") (pinfunction "AN_5") (pintype "passive"))
    )
    (net (code "70") (name "unconnected-(U$8-PW-Pad6)") (class "Default")
      (node (ref "U$8") (pin "6") (pinfunction "PW_6") (pintype "passive"))
    )
  )
)
